# LAB-02_Assignment.net
KiCad netlist of a schematic drawn in Altium Designer
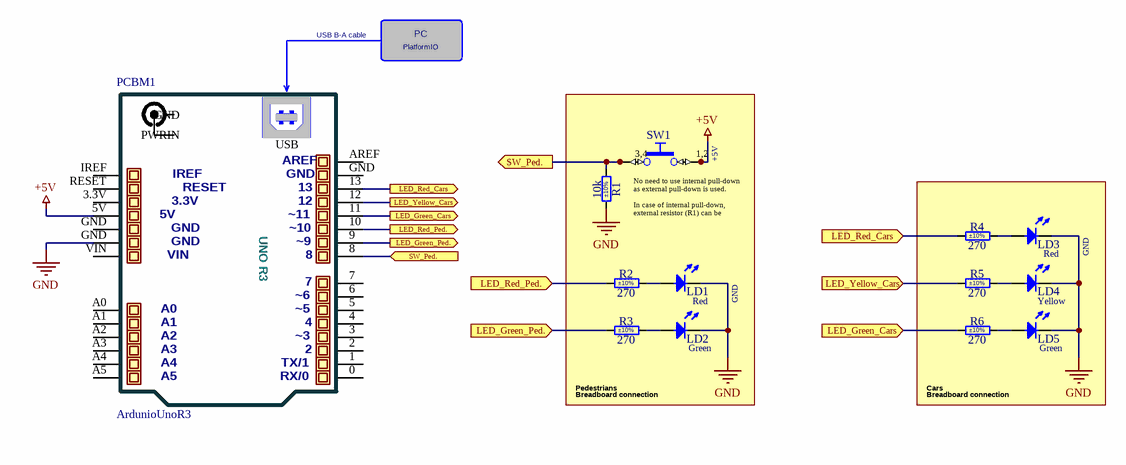
[diagram p0: LAB-02 Assignment.SchDoc]

(export (version "E")
  (design (tool "Eeschema 10.0.6"))
  (components
    (comp (ref "LD1")
      (value "Red")
      (footprint "LED_DIALIGHT_561-2201-050F")
      (description "LED Green 1C 2A")
      (fields
        (field (name "PART NUMBER") "LED_DIALIGHT_561-2201-050F")
        (field (name "MANUFACTURER") "DIALIGHT")
        (field (name "AUTHOR") "CERN DEM JLC")
      )
      (libsource (lib "ICs And Semiconductors") (part "LED Green 1C 2A"))
    )
    (comp (ref "LD2")
      (value "Green")
      (footprint "LED_DIALIGHT_561-2201-050F")
      (description "LED Green 1C 2A")
      (fields
        (field (name "PART NUMBER") "LED_DIALIGHT_561-2201-050F")
        (field (name "MANUFACTURER") "DIALIGHT")
        (field (name "AUTHOR") "CERN DEM JLC")
      )
      (libsource (lib "ICs And Semiconductors") (part "LED Green 1C 2A"))
    )
    (comp (ref "LD3")
      (value "Red")
      (footprint "LED_DIALIGHT_561-2201-050F")
      (description "LED Green 1C 2A")
      (fields
        (field (name "PART NUMBER") "LED_DIALIGHT_561-2201-050F")
        (field (name "MANUFACTURER") "DIALIGHT")
        (field (name "AUTHOR") "CERN DEM JLC")
      )
      (libsource (lib "ICs And Semiconductors") (part "LED Green 1C 2A"))
    )
    (comp (ref "LD4")
      (value "Yellow")
      (footprint "LED_DIALIGHT_561-2201-050F")
      (description "LED Green 1C 2A")
      (fields
        (field (name "PART NUMBER") "LED_DIALIGHT_561-2201-050F")
        (field (name "MANUFACTURER") "DIALIGHT")
        (field (name "AUTHOR") "CERN DEM JLC")
      )
      (libsource (lib "ICs And Semiconductors") (part "LED Green 1C 2A"))
    )
    (comp (ref "LD5")
      (value "Green")
      (footprint "LED_DIALIGHT_561-2201-050F")
      (description "LED Green 1C 2A")
      (fields
        (field (name "PART NUMBER") "LED_DIALIGHT_561-2201-050F")
        (field (name "MANUFACTURER") "DIALIGHT")
        (field (name "AUTHOR") "CERN DEM JLC")
      )
      (libsource (lib "ICs And Semiconductors") (part "LED Green 1C 2A"))
    )
    (comp (ref "PCBM1")
      (value "ArdunioUnoR3")
      (description "ArdunioUnoR3 Universal SCH Symbol \r\n(C) 230232")
      (libsource (lib "ArduinoUnoR3") (part "ArdunioUnoR3"))
    )
    (comp (ref "R1")
      (value "10k")
      (footprint "RESC3216X65N")
      (description "Resistor - 0.1%")
      (fields
        (field (name "TOLERANCE") "±10%")
        (field (name "PART NUMBER") "R1206_270R_0.1%_0.25W_25PPM")
        (field (name "POWER") "0.25W")
        (field (name "AUTHOR") "CERN DEM JLC")
      )
      (libsource (lib "Resistors") (part "Resistor - 0.1%"))
    )
    (comp (ref "R2")
      (value "270")
      (footprint "RESC3216X65N")
      (description "Resistor - 0.1%")
      (fields
        (field (name "TOLERANCE") "±10%")
        (field (name "PART NUMBER") "R1206_270R_0.1%_0.25W_25PPM")
        (field (name "POWER") "0.25W")
        (field (name "AUTHOR") "CERN DEM JLC")
      )
      (libsource (lib "Resistors") (part "Resistor - 0.1%"))
    )
    (comp (ref "R3")
      (value "270")
      (footprint "RESC3216X65N")
      (description "Resistor - 0.1%")
      (fields
        (field (name "TOLERANCE") "±10%")
        (field (name "PART NUMBER") "R1206_270R_0.1%_0.25W_25PPM")
        (field (name "POWER") "0.25W")
        (field (name "AUTHOR") "CERN DEM JLC")
      )
      (libsource (lib "Resistors") (part "Resistor - 0.1%"))
    )
    (comp (ref "R4")
      (value "270")
      (footprint "RESC3216X65N")
      (description "Resistor - 0.1%")
      (fields
        (field (name "TOLERANCE") "±10%")
        (field (name "PART NUMBER") "R1206_270R_0.1%_0.25W_25PPM")
        (field (name "POWER") "0.25W")
        (field (name "AUTHOR") "CERN DEM JLC")
      )
      (libsource (lib "Resistors") (part "Resistor - 0.1%"))
    )
    (comp (ref "R5")
      (value "270")
      (footprint "RESC3216X65N")
      (description "Resistor - 0.1%")
      (fields
        (field (name "TOLERANCE") "±10%")
        (field (name "PART NUMBER") "R1206_270R_0.1%_0.25W_25PPM")
        (field (name "POWER") "0.25W")
        (field (name "AUTHOR") "CERN DEM JLC")
      )
      (libsource (lib "Resistors") (part "Resistor - 0.1%"))
    )
    (comp (ref "R6")
      (value "270")
      (footprint "RESC3216X65N")
      (description "Resistor - 0.1%")
      (fields
        (field (name "TOLERANCE") "±10%")
        (field (name "PART NUMBER") "R1206_270R_0.1%_0.25W_25PPM")
        (field (name "POWER") "0.25W")
        (field (name "AUTHOR") "CERN DEM JLC")
      )
      (libsource (lib "Resistors") (part "Resistor - 0.1%"))
    )
    (comp (ref "SW1")
      (value "Push Button")
      (footprint "PB_ALPS_SKHHDTA010")
      (description "Push-Button Switch SPDT")
      (fields
        (field (name "PART NUMBER") "PB_ALPS_SKHHDTA010")
        (field (name "MANUFACTURER") "ALPS")
        (field (name "AUTHOR") "CERN DEM JLC")
      )
      (libsource (lib "Eletro-mechanical") (part "PB SPST 12NO-34NO"))
    )
  )
  (nets
    (net (code "1") (name "+5V") (class "Default")
      (node (ref "PCBM1") (pin "5V") (pinfunction "5V_5V") (pintype "passive"))
      (node (ref "SW1") (pin "1") (pinfunction "1_1") (pintype "bidirectional"))
      (node (ref "SW1") (pin "2") (pinfunction "2_2") (pintype "bidirectional"))
    )
    (net (code "2") (name "/LED_Green_Cars") (class "Default")
      (node (ref "PCBM1") (pin "11") (pinfunction "11_11") (pintype "passive"))
      (node (ref "R6") (pin "1") (pinfunction "1_1") (pintype "passive"))
    )
    (net (code "3") (name "/LED_Green_Ped.") (class "Default")
      (node (ref "PCBM1") (pin "9") (pinfunction "9_9") (pintype "passive"))
      (node (ref "R3") (pin "1") (pinfunction "1_1") (pintype "passive"))
    )
    (net (code "4") (name "/LED_Red_Cars") (class "Default")
      (node (ref "PCBM1") (pin "13") (pinfunction "13_13") (pintype "passive"))
      (node (ref "R4") (pin "1") (pinfunction "1_1") (pintype "passive"))
    )
    (net (code "5") (name "/LED_Red_Ped.") (class "Default")
      (node (ref "PCBM1") (pin "10") (pinfunction "10_10") (pintype "passive"))
      (node (ref "R2") (pin "1") (pinfunction "1_1") (pintype "passive"))
    )
    (net (code "6") (name "/LED_Yellow_Cars") (class "Default")
      (node (ref "PCBM1") (pin "12") (pinfunction "12_12") (pintype "passive"))
      (node (ref "R5") (pin "1") (pinfunction "1_1") (pintype "passive"))
    )
    (net (code "7") (name "/SW_Ped.") (class "Default")
      (node (ref "PCBM1") (pin "8") (pinfunction "8_8") (pintype "passive"))
      (node (ref "R1") (pin "2") (pinfunction "2_2") (pintype "passive"))
      (node (ref "SW1") (pin "3") (pinfunction "3_3") (pintype "bidirectional"))
      (node (ref "SW1") (pin "4") (pinfunction "4_4") (pintype "bidirectional"))
    )
    (net (code "8") (name "GND") (class "Default")
      (node (ref "LD1") (pin "1") (pinfunction "C_1") (pintype "passive"))
      (node (ref "LD2") (pin "1") (pinfunction "C_1") (pintype "passive"))
      (node (ref "LD3") (pin "1") (pinfunction "C_1") (pintype "passive"))
      (node (ref "LD4") (pin "1") (pinfunction "C_1") (pintype "passive"))
      (node (ref "LD5") (pin "1") (pinfunction "C_1") (pintype "passive"))
      (node (ref "PCBM1") (pin "GND") (pinfunction "GND_GND") (pintype "passive"))
      (node (ref "R1") (pin "1") (pinfunction "1_1") (pintype "passive"))
    )
    (net (code "9") (name "Net-(LD1-A)") (class "Default")
      (node (ref "LD1") (pin "2") (pinfunction "A_2") (pintype "passive"))
      (node (ref "R2") (pin "2") (pinfunction "2_2") (pintype "passive"))
    )
    (net (code "10") (name "Net-(LD2-A)") (class "Default")
      (node (ref "LD2") (pin "2") (pinfunction "A_2") (pintype "passive"))
      (node (ref "R3") (pin "2") (pinfunction "2_2") (pintype "passive"))
    )
    (net (code "11") (name "Net-(LD3-A)") (class "Default")
      (node (ref "LD3") (pin "2") (pinfunction "A_2") (pintype "passive"))
      (node (ref "R4") (pin "2") (pinfunction "2_2") (pintype "passive"))
    )
    (net (code "12") (name "Net-(LD4-A)") (class "Default")
      (node (ref "LD4") (pin "2") (pinfunction "A_2") (pintype "passive"))
      (node (ref "R5") (pin "2") (pinfunction "2_2") (pintype "passive"))
    )
    (net (code "13") (name "Net-(LD5-A)") (class "Default")
      (node (ref "LD5") (pin "2") (pinfunction "A_2") (pintype "passive"))
      (node (ref "R6") (pin "2") (pinfunction "2_2") (pintype "passive"))
    )
    (net (code "14") (name "unconnected-(PCBM1-Pad0)") (class "Default")
      (node (ref "PCBM1") (pin "0") (pinfunction "0_0") (pintype "passive"))
    )
    (net (code "15") (name "unconnected-(PCBM1-Pad1)") (class "Default")
      (node (ref "PCBM1") (pin "1") (pinfunction "1_1") (pintype "passive"))
    )
    (net (code "16") (name "unconnected-(PCBM1-Pad2)") (class "Default")
      (node (ref "PCBM1") (pin "2") (pinfunction "2_2") (pintype "passive"))
    )
    (net (code "17") (name "unconnected-(PCBM1-Pad3)") (class "Default")
      (node (ref "PCBM1") (pin "3") (pinfunction "3_3") (pintype "passive"))
    )
    (net (code "18") (name "unconnected-(PCBM1-Pad3.3V)") (class "Default")
      (node (ref "PCBM1") (pin "3.3V") (pinfunction "3.3V_3.3V") (pintype "passive"))
    )
    (net (code "19") (name "unconnected-(PCBM1-Pad4)") (class "Default")
      (node (ref "PCBM1") (pin "4") (pinfunction "4_4") (pintype "passive"))
    )
    (net (code "20") (name "unconnected-(PCBM1-Pad5)") (class "Default")
      (node (ref "PCBM1") (pin "5") (pinfunction "5_5") (pintype "passive"))
    )
    (net (code "21") (name "unconnected-(PCBM1-Pad6)") (class "Default")
      (node (ref "PCBM1") (pin "6") (pinfunction "6_6") (pintype "passive"))
    )
    (net (code "22") (name "unconnected-(PCBM1-Pad7)") (class "Default")
      (node (ref "PCBM1") (pin "7") (pinfunction "7_7") (pintype "passive"))
    )
    (net (code "23") (name "unconnected-(PCBM1-PadA0)") (class "Default")
      (node (ref "PCBM1") (pin "A0") (pinfunction "A0_A0") (pintype "passive"))
    )
    (net (code "24") (name "unconnected-(PCBM1-PadA1)") (class "Default")
      (node (ref "PCBM1") (pin "A1") (pinfunction "A1_A1") (pintype "passive"))
    )
    (net (code "25") (name "unconnected-(PCBM1-PadA2)") (class "Default")
      (node (ref "PCBM1") (pin "A2") (pinfunction "A2_A2") (pintype "passive"))
    )
    (net (code "26") (name "unconnected-(PCBM1-PadA3)") (class "Default")
      (node (ref "PCBM1") (pin "A3") (pinfunction "A3_A3") (pintype "passive"))
    )
    (net (code "27") (name "unconnected-(PCBM1-PadA4)") (class "Default")
      (node (ref "PCBM1") (pin "A4") (pinfunction "A4_A4") (pintype "passive"))
    )
    (net (code "28") (name "unconnected-(PCBM1-PadA5)") (class "Default")
      (node (ref "PCBM1") (pin "A5") (pinfunction "A5_A5") (pintype "passive"))
    )
    (net (code "29") (name "unconnected-(PCBM1-PadAREF)") (class "Default")
      (node (ref "PCBM1") (pin "AREF") (pinfunction "AREF_AREF") (pintype "passive"))
    )
    (net (code "30") (name "unconnected-(PCBM1-PadGND)") (class "Default")
      (node (ref "PCBM1") (pin "GND") (pinfunction "GND_GND") (pintype "passive"))
    )
    (net (code "31") (name "unconnected-(PCBM1-PadGND)_1") (class "Default")
      (node (ref "PCBM1") (pin "GND") (pinfunction "GND_GND") (pintype "passive"))
    )
    (net (code "32") (name "unconnected-(PCBM1-PadIREF)") (class "Default")
      (node (ref "PCBM1") (pin "IREF") (pinfunction "IREF_IREF") (pintype "passive"))
    )
    (net (code "33") (name "unconnected-(PCBM1-PadRESET)") (class "Default")
      (node (ref "PCBM1") (pin "RESET") (pinfunction "RESET_RESET") (pintype "passive"))
    )
    (net (code "34") (name "unconnected-(PCBM1-PadVIN)") (class "Default")
      (node (ref "PCBM1") (pin "VIN") (pinfunction "VIN_VIN") (pintype "passive"))
    )
  )
)
